# gyro_board.net
KiCad netlist of a schematic drawn in EAGLE
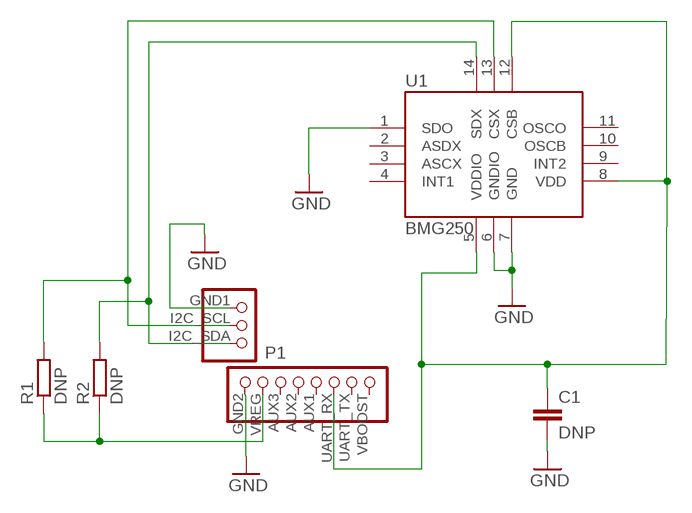
[diagram p0: schematic, sheet 1]

(export (version "E")
  (design (tool "Eeschema 10.0.6"))
  (components
    (comp (ref "C1")
      (value "DNP")
      (footprint "eagle-import:C0603")
      (libsource (lib "eagle-import") (part "C-EUC0603"))
    )
    (comp (ref "P1")
      (value "WISP_HEADER")
      (footprint "eagle-import:PINHEAD_WISP3X8-1.27MM")
      (libsource (lib "eagle-import") (part "WISP_HEADER"))
    )
    (comp (ref "R1")
      (value "DNP")
      (footprint "eagle-import:R0603")
      (libsource (lib "eagle-import") (part "R-EU_R0603"))
    )
    (comp (ref "R2")
      (value "DNP")
      (footprint "eagle-import:R0603")
      (libsource (lib "eagle-import") (part "R-EU_R0603"))
    )
    (comp (ref "U1")
      (value "BMG250")
      (footprint "eagle-import:LGA14L")
      (libsource (lib "eagle-import") (part "BGM250"))
    )
  )
  (nets
    (net (code "1") (name "GND") (class "Default")
      (node (ref "C1") (pin "2") (pinfunction "2_2") (pintype "passive"))
      (node (ref "P1") (pin "GND1") (pinfunction "GND1_GND1") (pintype "passive"))
      (node (ref "P1") (pin "GND2") (pinfunction "GND2_GND2") (pintype "passive"))
      (node (ref "U1") (pin "1") (pinfunction "SDO_1") (pintype "bidirectional"))
      (node (ref "U1") (pin "6") (pinfunction "GNDIO_6") (pintype "bidirectional"))
      (node (ref "U1") (pin "7") (pinfunction "GND_7") (pintype "bidirectional"))
    )
    (net (code "2") (name "Net-(P1-PadVREG)") (class "Default")
      (node (ref "P1") (pin "VREG") (pinfunction "VREG_VREG") (pintype "passive"))
      (node (ref "R1") (pin "1") (pinfunction "1_1") (pintype "passive"))
      (node (ref "R2") (pin "1") (pinfunction "1_1") (pintype "passive"))
    )
    (net (code "3") (name "Net-(U1-CSB)") (class "Default")
      (node (ref "C1") (pin "1") (pinfunction "1_1") (pintype "passive"))
      (node (ref "P1") (pin "UART_RX") (pinfunction "UART_RX_UART_RX") (pintype "passive"))
      (node (ref "U1") (pin "12") (pinfunction "CSB_12") (pintype "bidirectional"))
      (node (ref "U1") (pin "5") (pinfunction "VDDIO_5") (pintype "bidirectional"))
      (node (ref "U1") (pin "8") (pinfunction "VDD_8") (pintype "bidirectional"))
    )
    (net (code "4") (name "Net-(U1-CSX)") (class "Default")
      (node (ref "P1") (pin "I2C_SCL") (pinfunction "I2C_SCL_I2C_SCL") (pintype "passive"))
      (node (ref "R1") (pin "2") (pinfunction "2_2") (pintype "passive"))
      (node (ref "U1") (pin "13") (pinfunction "CSX_13") (pintype "bidirectional"))
    )
    (net (code "5") (name "Net-(U1-SDX)") (class "Default")
      (node (ref "P1") (pin "I2C_SDA") (pinfunction "I2C_SDA_I2C_SDA") (pintype "passive"))
      (node (ref "R2") (pin "2") (pinfunction "2_2") (pintype "passive"))
      (node (ref "U1") (pin "14") (pinfunction "SDX_14") (pintype "bidirectional"))
    )
    (net (code "6") (name "unconnected-(P1-PadAUX1)") (class "Default")
      (node (ref "P1") (pin "AUX1") (pinfunction "AUX1_AUX1") (pintype "passive"))
    )
    (net (code "7") (name "unconnected-(P1-PadAUX2)") (class "Default")
      (node (ref "P1") (pin "AUX2") (pinfunction "AUX2_AUX2") (pintype "passive"))
    )
    (net (code "8") (name "unconnected-(P1-PadAUX3)") (class "Default")
      (node (ref "P1") (pin "AUX3") (pinfunction "AUX3_AUX3") (pintype "passive"))
    )
    (net (code "9") (name "unconnected-(P1-PadUART_TX)") (class "Default")
      (node (ref "P1") (pin "UART_TX") (pinfunction "UART_TX_UART_TX") (pintype "passive"))
    )
    (net (code "10") (name "unconnected-(P1-PadVBOOST)") (class "Default")
      (node (ref "P1") (pin "VBOOST") (pinfunction "VBOOST_VBOOST") (pintype "passive"))
    )
    (net (code "11") (name "unconnected-(U1-ASCX-Pad3)") (class "Default")
      (node (ref "U1") (pin "3") (pinfunction "ASCX_3") (pintype "bidirectional"))
    )
    (net (code "12") (name "unconnected-(U1-ASDX-Pad2)") (class "Default")
      (node (ref "U1") (pin "2") (pinfunction "ASDX_2") (pintype "bidirectional"))
    )
    (net (code "13") (name "unconnected-(U1-INT1-Pad4)") (class "Default")
      (node (ref "U1") (pin "4") (pinfunction "INT1_4") (pintype "bidirectional"))
    )
    (net (code "14") (name "unconnected-(U1-INT2-Pad9)") (class "Default")
      (node (ref "U1") (pin "9") (pinfunction "INT2_9") (pintype "bidirectional"))
    )
    (net (code "15") (name "unconnected-(U1-OSCB-Pad10)") (class "Default")
      (node (ref "U1") (pin "10") (pinfunction "OSCB_10") (pintype "bidirectional"))
    )
    (net (code "16") (name "unconnected-(U1-OSCO-Pad11)") (class "Default")
      (node (ref "U1") (pin "11") (pinfunction "OSCO_11") (pintype "bidirectional"))
    )
  )
)
